# rx_switch.net
KiCad netlist of a schematic drawn in EAGLE
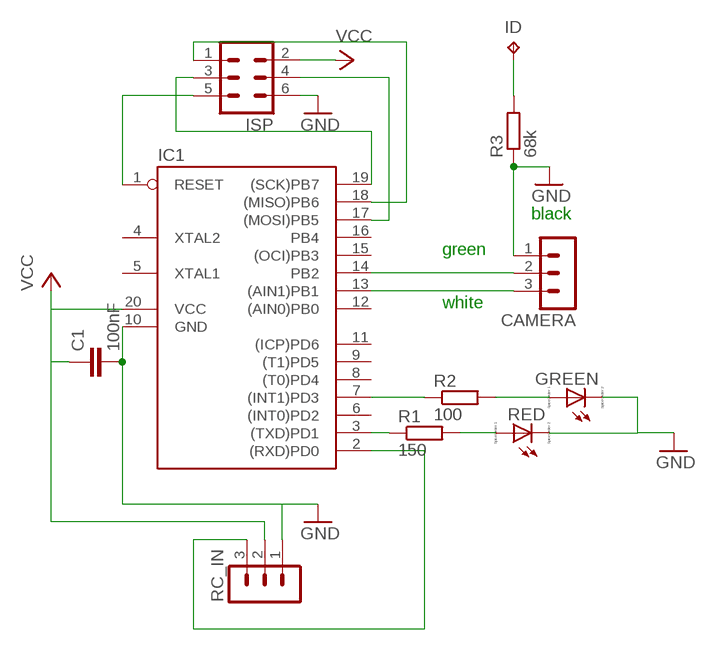
[diagram p0: schematic, sheet 1]

(export (version "E")
  (design (tool "Eeschema 10.0.6"))
  (components
    (comp (ref "C1")
      (value "100nF")
      (footprint "eagle-import:C0805")
      (libsource (lib "eagle-import") (part "C-EUC0805"))
    )
    (comp (ref "CAMERA")
      (value "MA03-1")
      (footprint "eagle-import:MA03-1")
      (libsource (lib "eagle-import") (part "MA03-1"))
    )
    (comp (ref "GREEN")
      (value "LED_E")
      (footprint "eagle-import:LED_1206")
      (libsource (lib "eagle-import") (part "LED_E"))
    )
    (comp (ref "IC1")
      (value "AT90S2313S")
      (footprint "eagle-import:SO20L")
      (libsource (lib "eagle-import") (part "AT90S2313S"))
    )
    (comp (ref "ID")
      (value "TPPAD1-13")
      (footprint "eagle-import:P1-13")
      (libsource (lib "eagle-import") (part "TPPAD1-13"))
    )
    (comp (ref "ISP")
      (value "MA03-2")
      (footprint "eagle-import:MA03-2")
      (libsource (lib "eagle-import") (part "MA03-2"))
    )
    (comp (ref "R1")
      (value "150")
      (footprint "eagle-import:R1206")
      (libsource (lib "eagle-import") (part "R-EU_R1206"))
    )
    (comp (ref "R2")
      (value "100")
      (footprint "eagle-import:R1206")
      (libsource (lib "eagle-import") (part "R-EU_R1206"))
    )
    (comp (ref "R3")
      (value "68k")
      (footprint "eagle-import:R1206")
      (libsource (lib "eagle-import") (part "R-EU_R1206"))
    )
    (comp (ref "RC_IN")
      (value "MA03-1")
      (footprint "eagle-import:MA03-1")
      (libsource (lib "eagle-import") (part "MA03-1"))
    )
    (comp (ref "RED")
      (value "LED_E")
      (footprint "eagle-import:LED_1206")
      (libsource (lib "eagle-import") (part "LED_E"))
    )
  )
  (nets
    (net (code "1") (name "GND") (class "Default")
      (node (ref "C1") (pin "2") (pinfunction "2_2") (pintype "passive"))
      (node (ref "CAMERA") (pin "1") (pinfunction "1_1") (pintype "passive"))
      (node (ref "GREEN") (pin "C") (pinfunction "C_C") (pintype "passive"))
      (node (ref "IC1") (pin "10") (pinfunction "GND_10") (pintype "power_in"))
      (node (ref "ISP") (pin "6") (pinfunction "6_6") (pintype "passive"))
      (node (ref "R3") (pin "1") (pinfunction "1_1") (pintype "passive"))
      (node (ref "RC_IN") (pin "1") (pinfunction "1_1") (pintype "passive"))
      (node (ref "RED") (pin "C") (pinfunction "C_C") (pintype "passive"))
    )
    (net (code "2") (name "Net-(GREEN-PadA)") (class "Default")
      (node (ref "GREEN") (pin "A") (pinfunction "A_A") (pintype "passive"))
      (node (ref "R2") (pin "2") (pinfunction "2_2") (pintype "passive"))
    )
    (net (code "3") (name "Net-(IC1-(AIN1)PB1)") (class "Default")
      (node (ref "CAMERA") (pin "3") (pinfunction "3_3") (pintype "passive"))
      (node (ref "IC1") (pin "13") (pinfunction "(AIN1)PB1_13") (pintype "bidirectional"))
    )
    (net (code "4") (name "Net-(IC1-(INT1)PD3)") (class "Default")
      (node (ref "IC1") (pin "7") (pinfunction "(INT1)PD3_7") (pintype "bidirectional"))
      (node (ref "R2") (pin "1") (pinfunction "1_1") (pintype "passive"))
    )
    (net (code "5") (name "Net-(IC1-(MISO)PB6)") (class "Default")
      (node (ref "IC1") (pin "18") (pinfunction "(MISO)PB6_18") (pintype "bidirectional"))
      (node (ref "ISP") (pin "1") (pinfunction "1_1") (pintype "passive"))
    )
    (net (code "6") (name "Net-(IC1-(MOSI)PB5)") (class "Default")
      (node (ref "IC1") (pin "17") (pinfunction "(MOSI)PB5_17") (pintype "bidirectional"))
      (node (ref "ISP") (pin "4") (pinfunction "4_4") (pintype "passive"))
    )
    (net (code "7") (name "Net-(IC1-(RXD)PD0)") (class "Default")
      (node (ref "IC1") (pin "2") (pinfunction "(RXD)PD0_2") (pintype "bidirectional"))
      (node (ref "RC_IN") (pin "3") (pinfunction "3_3") (pintype "passive"))
    )
    (net (code "8") (name "Net-(IC1-(SCK)PB7)") (class "Default")
      (node (ref "IC1") (pin "19") (pinfunction "(SCK)PB7_19") (pintype "bidirectional"))
      (node (ref "ISP") (pin "3") (pinfunction "3_3") (pintype "passive"))
    )
    (net (code "9") (name "Net-(IC1-(TXD)PD1)") (class "Default")
      (node (ref "IC1") (pin "3") (pinfunction "(TXD)PD1_3") (pintype "bidirectional"))
      (node (ref "R1") (pin "1") (pinfunction "1_1") (pintype "passive"))
    )
    (net (code "10") (name "Net-(IC1-PB2)") (class "Default")
      (node (ref "CAMERA") (pin "2") (pinfunction "2_2") (pintype "passive"))
      (node (ref "IC1") (pin "14") (pinfunction "PB2_14") (pintype "bidirectional"))
    )
    (net (code "11") (name "Net-(IC1-RESET)") (class "Default")
      (node (ref "IC1") (pin "1") (pinfunction "RESET_1") (pintype "bidirectional"))
      (node (ref "ISP") (pin "5") (pinfunction "5_5") (pintype "passive"))
    )
    (net (code "12") (name "Net-(ID-PadTP)") (class "Default")
      (node (ref "ID") (pin "TP") (pinfunction "TP_TP") (pintype "input"))
      (node (ref "R3") (pin "2") (pinfunction "2_2") (pintype "passive"))
    )
    (net (code "13") (name "Net-(R1-Pad2)") (class "Default")
      (node (ref "R1") (pin "2") (pinfunction "2_2") (pintype "passive"))
      (node (ref "RED") (pin "A") (pinfunction "A_A") (pintype "passive"))
    )
    (net (code "14") (name "VCC") (class "Default")
      (node (ref "C1") (pin "1") (pinfunction "1_1") (pintype "passive"))
      (node (ref "IC1") (pin "20") (pinfunction "VCC_20") (pintype "power_in"))
      (node (ref "ISP") (pin "2") (pinfunction "2_2") (pintype "passive"))
      (node (ref "RC_IN") (pin "2") (pinfunction "2_2") (pintype "passive"))
    )
    (net (code "15") (name "unconnected-(IC1-(AIN0)PB0-Pad12)") (class "Default")
      (node (ref "IC1") (pin "12") (pinfunction "(AIN0)PB0_12") (pintype "bidirectional"))
    )
    (net (code "16") (name "unconnected-(IC1-(ICP)PD6-Pad11)") (class "Default")
      (node (ref "IC1") (pin "11") (pinfunction "(ICP)PD6_11") (pintype "bidirectional"))
    )
    (net (code "17") (name "unconnected-(IC1-(INT0)PD2-Pad6)") (class "Default")
      (node (ref "IC1") (pin "6") (pinfunction "(INT0)PD2_6") (pintype "bidirectional"))
    )
    (net (code "18") (name "unconnected-(IC1-(OCI)PB3-Pad15)") (class "Default")
      (node (ref "IC1") (pin "15") (pinfunction "(OCI)PB3_15") (pintype "bidirectional"))
    )
    (net (code "19") (name "unconnected-(IC1-(T0)PD4-Pad8)") (class "Default")
      (node (ref "IC1") (pin "8") (pinfunction "(T0)PD4_8") (pintype "bidirectional"))
    )
    (net (code "20") (name "unconnected-(IC1-(T1)PD5-Pad9)") (class "Default")
      (node (ref "IC1") (pin "9") (pinfunction "(T1)PD5_9") (pintype "bidirectional"))
    )
    (net (code "21") (name "unconnected-(IC1-PB4-Pad16)") (class "Default")
      (node (ref "IC1") (pin "16") (pinfunction "PB4_16") (pintype "bidirectional"))
    )
    (net (code "22") (name "unconnected-(IC1-XTAL1-Pad5)") (class "Default")
      (node (ref "IC1") (pin "5") (pinfunction "XTAL1_5") (pintype "bidirectional"))
    )
    (net (code "23") (name "unconnected-(IC1-XTAL2-Pad4)") (class "Default")
      (node (ref "IC1") (pin "4") (pinfunction "XTAL2_4") (pintype "bidirectional"))
    )
  )
)
